# CanTransceiver.net
KiCad netlist of a schematic drawn in Altium Designer
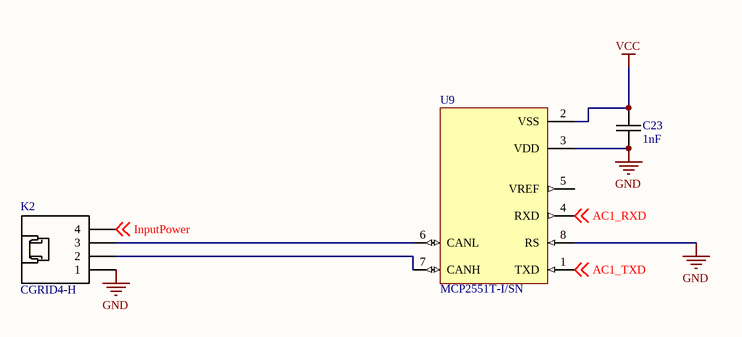
[diagram p0: CanTransceiver.SchDoc]

(export (version "E")
  (design (tool "Eeschema 10.0.6"))
  (components
    (comp (ref "C23")
      (value "1nF")
      (footprint "0603C-GENERIC")
      (description "CAPACITOR 0603 CERAMIC")
      (libsource (lib "vh_altium_library") (part "0603C-000"))
    )
    (comp (ref "K2")
      (value "CGRID4-H")
      (footprint "CGRID-4H")
      (description "MOLEX GC/WALDOM CGRID CONNECTOR 4 PIN")
      (libsource (lib "vh_altium_library") (part "CGRID4-H"))
    )
    (comp (ref "U9")
      (value "MCP2551T-I/SN")
      (footprint "SOIC-SN8_N")
      (description "High-Speed CAN Transceiver, 8-Pin SOIC, Industrial Temperature, Tape and Reel")
      (fields (field (name "PUBLISHER") "Altium Limited"))
      (libsource (lib "Microchip Interface") (part "MCP2551T-I/SN"))
    )
  )
  (nets
    (net (code "1") (name "AC1_RXD") (class "Default")
      (node (ref "U9") (pin "4") (pinfunction "RXD_4") (pintype "output"))
    )
    (net (code "2") (name "AC1_TXD") (class "Default")
      (node (ref "U9") (pin "1") (pinfunction "TXD_1") (pintype "input"))
    )
    (net (code "3") (name "GND") (class "Default")
      (node (ref "C23") (pin "2") (pintype "passive"))
      (node (ref "K2") (pin "1") (pinfunction "1_1") (pintype "passive"))
      (node (ref "U9") (pin "3") (pinfunction "VDD_3") (pintype "power_in"))
      (node (ref "U9") (pin "8") (pinfunction "RS_8") (pintype "input"))
    )
    (net (code "4") (name "InputPower") (class "Default")
      (node (ref "K2") (pin "4") (pinfunction "4_4") (pintype "passive"))
    )
    (net (code "5") (name "Net-(U9-CANH)") (class "Default")
      (node (ref "K2") (pin "2") (pinfunction "2_2") (pintype "passive"))
      (node (ref "U9") (pin "7") (pinfunction "CANH_7") (pintype "bidirectional"))
    )
    (net (code "6") (name "Net-(U9-CANL)") (class "Default")
      (node (ref "K2") (pin "3") (pinfunction "3_3") (pintype "passive"))
      (node (ref "U9") (pin "6") (pinfunction "CANL_6") (pintype "bidirectional"))
    )
    (net (code "7") (name "VCC") (class "Default")
      (node (ref "C23") (pin "1") (pintype "passive"))
      (node (ref "U9") (pin "2") (pinfunction "VSS_2") (pintype "power_in"))
    )
    (net (code "8") (name "unconnected-(U9-VREF-Pad5)") (class "Default")
      (node (ref "U9") (pin "5") (pinfunction "VREF_5") (pintype "output"))
    )
  )
)
